# eeZeeTiny841.net
KiCad netlist of a schematic drawn in EAGLE
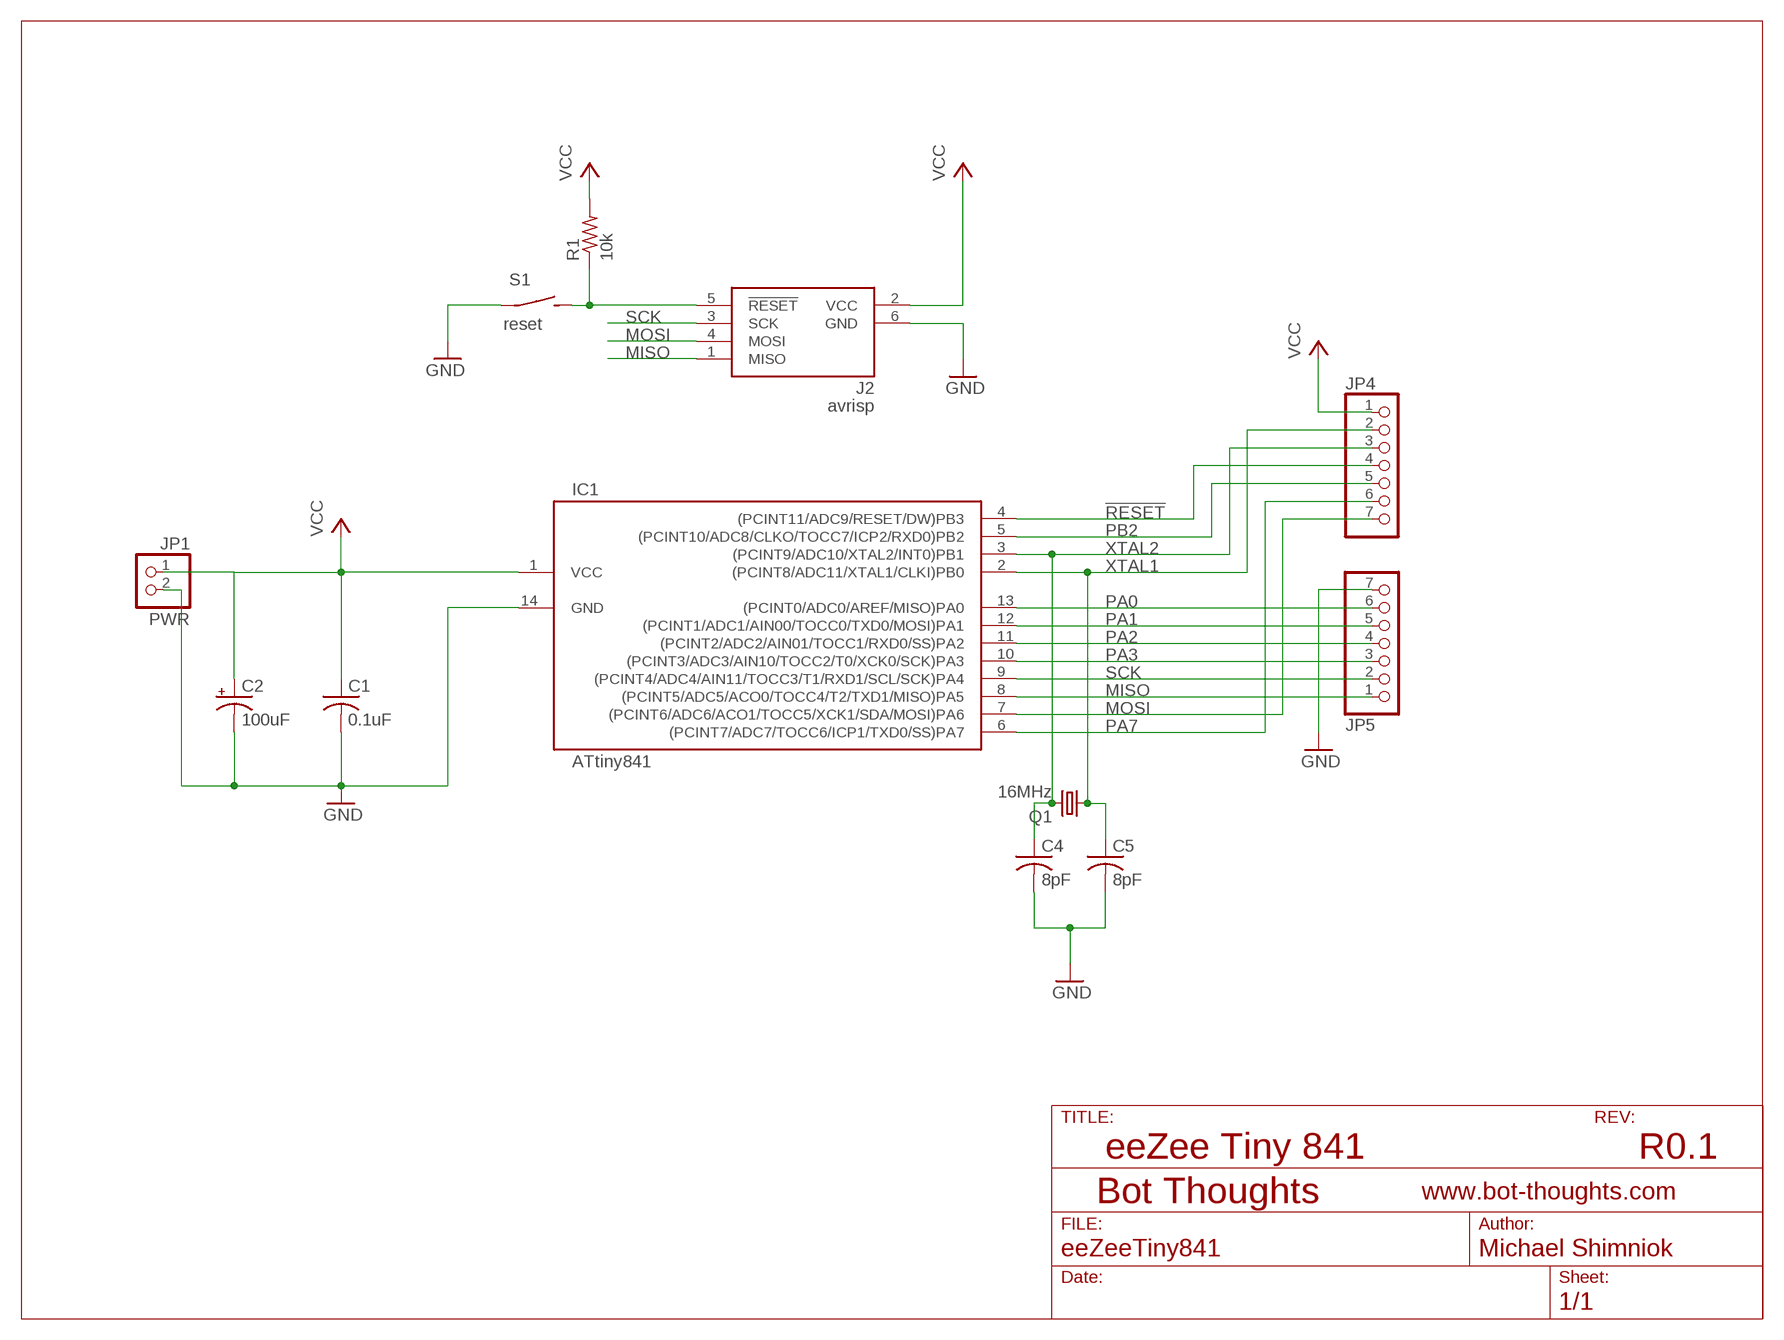
[diagram p0: schematic, sheet 1]

(export (version "E")
  (design (tool "Eeschema 10.0.6"))
  (components
    (comp (ref "C1")
      (value "0.1uF")
      (footprint "eagle-import:C0603")
      (fields (field (name "PARTNO") "0603YC104KAT2A"))
      (libsource (lib "eagle-import") (part "C-USC0603"))
    )
    (comp (ref "C2")
      (value "100uF")
      (footprint "eagle-import:SMC_B")
      (fields (field (name "PARTNO") "MCTT21X106M6R3CT"))
      (libsource (lib "eagle-import") (part "CAP_POL_SMC_B"))
    )
    (comp (ref "C4")
      (value "8pF")
      (footprint "eagle-import:C0603")
      (fields (field (name "PARTNO") "0603YC104KAT2A"))
      (libsource (lib "eagle-import") (part "C-USC0603"))
    )
    (comp (ref "C5")
      (value "8pF")
      (footprint "eagle-import:C0603")
      (fields (field (name "PARTNO") "0603YC104KAT2A"))
      (libsource (lib "eagle-import") (part "C-USC0603"))
    )
    (comp (ref "IC1")
      (value "ATtiny841")
      (footprint "eagle-import:SOIC14")
      (libsource (lib "eagle-import") (part "ATTINY441/841-SSU"))
    )
    (comp (ref "J2")
      (value "avrisp")
      (footprint "eagle-import:CON6P2R")
      (libsource (lib "eagle-import") (part "AVRISP6"))
    )
    (comp (ref "JP1")
      (value "PWR")
      (footprint "eagle-import:1X02-S")
      (libsource (lib "eagle-import") (part "PINHD-1X02_2.54-S"))
    )
    (comp (ref "JP4")
      (value "PINHD-1X07_2.54-S")
      (footprint "eagle-import:1X07-S")
      (libsource (lib "eagle-import") (part "PINHD-1X07_2.54-S"))
    )
    (comp (ref "JP5")
      (value "PINHD-1X07_2.54-S")
      (footprint "eagle-import:1X07-S")
      (libsource (lib "eagle-import") (part "PINHD-1X07_2.54-S"))
    )
    (comp (ref "Q1")
      (value "16MHz")
      (footprint "eagle-import:NDK_2PAD_5X3")
      (libsource (lib "eagle-import") (part "CRYSTALNDK5X3"))
    )
    (comp (ref "R1")
      (value "10k")
      (footprint "eagle-import:R0603")
      (fields (field (name "PARTNO") "ERJ-3GEYJ103V"))
      (libsource (lib "eagle-import") (part "R-US_R0603"))
    )
    (comp (ref "S1")
      (value "reset")
      (footprint "eagle-import:6MMTACTILE_RECT")
      (libsource (lib "eagle-import") (part "SPST_TAC_RECT1"))
    )
  )
  (nets
    (net (code "1") (name "/MISO") (class "Default")
      (node (ref "IC1") (pin "11") (pinfunction "(PCINT2/ADC2/AIN01/TOCC1/RXD0/SS)PA2_11") (pintype "bidirectional"))
      (node (ref "J2") (pin "1") (pinfunction "MISO_1") (pintype "input"))
      (node (ref "JP5") (pin "4") (pinfunction "4_4") (pintype "passive"))
    )
    (net (code "2") (name "/MOSI") (class "Default")
      (node (ref "IC1") (pin "12") (pinfunction "(PCINT1/ADC1/AIN00/TOCC0/TXD0/MOSI)PA1_12") (pintype "bidirectional"))
      (node (ref "J2") (pin "4") (pinfunction "MOSI_4") (pintype "output"))
      (node (ref "JP5") (pin "5") (pinfunction "5_5") (pintype "passive"))
    )
    (net (code "3") (name "/PA0") (class "Default")
      (node (ref "IC1") (pin "6") (pinfunction "(PCINT7/ADC7/TOCC6/ICP1/TXD0/SS)PA7_6") (pintype "bidirectional"))
      (node (ref "JP4") (pin "6") (pinfunction "6_6") (pintype "passive"))
    )
    (net (code "4") (name "/PA1") (class "Default")
      (node (ref "IC1") (pin "7") (pinfunction "(PCINT6/ADC6/ACO1/TOCC5/XCK1/SDA/MOSI)PA6_7") (pintype "bidirectional"))
      (node (ref "JP4") (pin "7") (pinfunction "7_7") (pintype "passive"))
    )
    (net (code "5") (name "/PA2") (class "Default")
      (node (ref "IC1") (pin "8") (pinfunction "(PCINT5/ADC5/ACO0/TOCC4/T2/TXD1/MISO)PA5_8") (pintype "bidirectional"))
      (node (ref "JP5") (pin "1") (pinfunction "1_1") (pintype "passive"))
    )
    (net (code "6") (name "/PA3") (class "Default")
      (node (ref "IC1") (pin "10") (pinfunction "(PCINT3/ADC3/AIN10/TOCC2/T0/XCK0/SCK)PA3_10") (pintype "bidirectional"))
      (node (ref "JP5") (pin "3") (pinfunction "3_3") (pintype "passive"))
    )
    (net (code "7") (name "/PA7") (class "Default")
      (node (ref "IC1") (pin "13") (pinfunction "(PCINT0/ADC0/AREF/MISO)PA0_13") (pintype "bidirectional"))
      (node (ref "JP5") (pin "6") (pinfunction "6_6") (pintype "passive"))
    )
    (net (code "8") (name "/PB2") (class "Default")
      (node (ref "IC1") (pin "5") (pinfunction "(PCINT10/ADC8/CLKO/TOCC7/ICP2/RXD0)PB2_5") (pintype "bidirectional"))
      (node (ref "JP4") (pin "5") (pinfunction "5_5") (pintype "passive"))
    )
    (net (code "9") (name "/SCK") (class "Default")
      (node (ref "IC1") (pin "9") (pinfunction "(PCINT4/ADC4/AIN11/TOCC3/T1/RXD1/SCL/SCK)PA4_9") (pintype "bidirectional"))
      (node (ref "J2") (pin "3") (pinfunction "SCK_3") (pintype "output"))
      (node (ref "JP5") (pin "2") (pinfunction "2_2") (pintype "passive"))
    )
    (net (code "10") (name "/XTAL1") (class "Default")
      (node (ref "C5") (pin "1") (pinfunction "1_1") (pintype "passive"))
      (node (ref "IC1") (pin "2") (pinfunction "(PCINT8/ADC11/XTAL1/CLKI)PB0_2") (pintype "bidirectional"))
      (node (ref "JP4") (pin "2") (pinfunction "2_2") (pintype "passive"))
      (node (ref "Q1") (pin "P$1") (pinfunction "1_P$1") (pintype "passive"))
    )
    (net (code "11") (name "/XTAL2") (class "Default")
      (node (ref "C4") (pin "1") (pinfunction "1_1") (pintype "passive"))
      (node (ref "IC1") (pin "3") (pinfunction "(PCINT9/ADC10/XTAL2/INT0)PB1_3") (pintype "bidirectional"))
      (node (ref "JP4") (pin "3") (pinfunction "3_3") (pintype "passive"))
      (node (ref "Q1") (pin "P$2") (pinfunction "2_P$2") (pintype "passive"))
    )
    (net (code "12") (name "/~{RESET}") (class "Default")
      (node (ref "IC1") (pin "4") (pinfunction "(PCINT11/ADC9/RESET/DW)PB3_4") (pintype "bidirectional"))
      (node (ref "J2") (pin "5") (pinfunction "~{RESET}_5") (pintype "output"))
      (node (ref "JP4") (pin "4") (pinfunction "4_4") (pintype "passive"))
      (node (ref "R1") (pin "1") (pinfunction "1_1") (pintype "passive"))
      (node (ref "S1") (pin "P$2") (pinfunction "S_P$2") (pintype "passive"))
    )
    (net (code "13") (name "GND") (class "Default")
      (node (ref "C1") (pin "2") (pinfunction "2_2") (pintype "passive"))
      (node (ref "C2") (pin "-") (pinfunction "-_-") (pintype "passive"))
      (node (ref "C4") (pin "2") (pinfunction "2_2") (pintype "passive"))
      (node (ref "C5") (pin "2") (pinfunction "2_2") (pintype "passive"))
      (node (ref "IC1") (pin "14") (pinfunction "GND_14") (pintype "bidirectional"))
      (node (ref "J2") (pin "6") (pinfunction "GND_6") (pintype "power_in"))
      (node (ref "JP1") (pin "2") (pinfunction "2_2") (pintype "passive"))
      (node (ref "JP5") (pin "7") (pinfunction "7_7") (pintype "passive"))
      (node (ref "S1") (pin "P$1") (pinfunction "P_P$1") (pintype "passive"))
    )
    (net (code "14") (name "VCC") (class "Default")
      (node (ref "C1") (pin "1") (pinfunction "1_1") (pintype "passive"))
      (node (ref "C2") (pin "+") (pinfunction "+_+") (pintype "passive"))
      (node (ref "IC1") (pin "1") (pinfunction "VCC_1") (pintype "bidirectional"))
      (node (ref "J2") (pin "2") (pinfunction "VCC_2") (pintype "power_in"))
      (node (ref "JP1") (pin "1") (pinfunction "1_1") (pintype "passive"))
      (node (ref "JP4") (pin "1") (pinfunction "1_1") (pintype "passive"))
      (node (ref "R1") (pin "2") (pinfunction "2_2") (pintype "passive"))
    )
  )
)
